# 5_Ble.net
KiCad netlist of a schematic drawn in Altium Designer
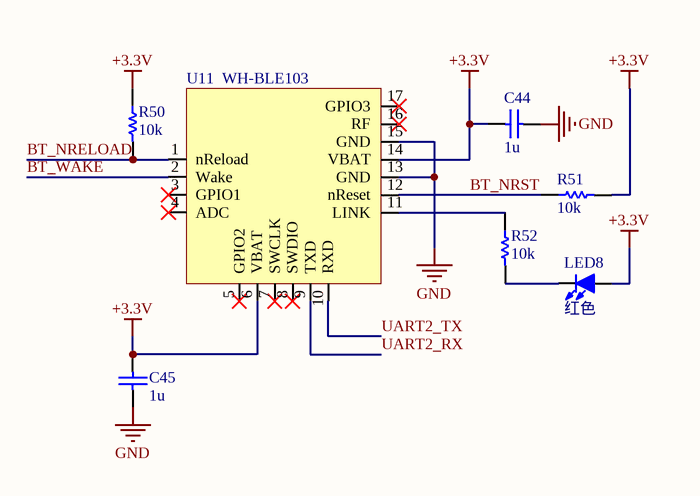
[diagram p0: 5_Ble.SchDoc]

(export (version "E")
  (design (tool "Eeschema 10.0.6"))
  (components
    (comp (ref "C44")
      (value "1u")
      (footprint "CAP_0603_SMD")
      (description "Capacitor, 0603, SMD")
      (fields (field (name "PUBLISHER") "Altium Limited"))
      (libsource (lib "myRLC") (part "CAP_0603_SMD"))
    )
    (comp (ref "C45")
      (value "1u")
      (footprint "CAP_0603_SMD")
      (description "Capacitor, 0603, SMD")
      (fields (field (name "PUBLISHER") "Altium Limited"))
      (libsource (lib "myRLC") (part "CAP_0603_SMD"))
    )
    (comp (ref "LED8")
      (value "红色")
      (footprint "LED0603_Y")
      (description "贴片LED")
      (libsource (lib "0.3 - LED发光二极管") (part "LED-SMD"))
    )
    (comp (ref "R50")
      (value "10k")
      (footprint "RES_0603_SMD")
      (description "Resistor, 0603, SMD")
      (fields (field (name "PUBLISHER") "Altium Limited"))
      (libsource (lib "myRLC") (part "RES_0603_SMD"))
    )
    (comp (ref "R51")
      (value "10k")
      (footprint "RES_0603_SMD")
      (description "Resistor, 0603, SMD")
      (fields (field (name "PUBLISHER") "Altium Limited"))
      (libsource (lib "myRLC") (part "RES_0603_SMD"))
    )
    (comp (ref "R52")
      (value "10k")
      (footprint "RES_0603_SMD")
      (description "Resistor, 0603, SMD")
      (fields (field (name "PUBLISHER") "Altium Limited"))
      (libsource (lib "myRLC") (part "RES_0603_SMD"))
    )
    (comp (ref "U11")
      (value "WH-BLE103")
      (footprint "WH-BLE103:PCBComponent_1")
      (libsource (lib "WH-BLE103") (part "WH-BLE103"))
    )
  )
  (nets
    (net (code "1") (name "+3.3V") (class "Default")
      (node (ref "C44") (pin "2") (pinfunction "2_2") (pintype "passive"))
      (node (ref "C45") (pin "1") (pinfunction "1_1") (pintype "passive"))
      (node (ref "LED8") (pin "1") (pinfunction "A_1") (pintype "passive"))
      (node (ref "R50") (pin "1") (pinfunction "1_1") (pintype "passive"))
      (node (ref "R51") (pin "2") (pinfunction "2_2") (pintype "passive"))
      (node (ref "U11") (pin "14") (pinfunction "VBAT_14") (pintype "passive"))
      (node (ref "U11") (pin "6") (pinfunction "VBAT_6") (pintype "passive"))
    )
    (net (code "2") (name "/BT_NRELOAD") (class "Default")
      (node (ref "R50") (pin "2") (pinfunction "2_2") (pintype "passive"))
      (node (ref "U11") (pin "1") (pinfunction "nReload_1") (pintype "passive"))
    )
    (net (code "3") (name "/BT_NRST") (class "Default")
      (node (ref "R51") (pin "1") (pinfunction "1_1") (pintype "passive"))
      (node (ref "U11") (pin "12") (pinfunction "nReset_12") (pintype "passive"))
    )
    (net (code "4") (name "/BT_WAKE") (class "Default")
      (node (ref "U11") (pin "2") (pinfunction "Wake_2") (pintype "passive"))
    )
    (net (code "5") (name "/UART2_RX") (class "Default")
      (node (ref "U11") (pin "9") (pinfunction "TXD_9") (pintype "passive"))
    )
    (net (code "6") (name "/UART2_TX") (class "Default")
      (node (ref "U11") (pin "10") (pinfunction "RXD_10") (pintype "passive"))
    )
    (net (code "7") (name "GND") (class "Default")
      (node (ref "C44") (pin "1") (pinfunction "1_1") (pintype "passive"))
      (node (ref "C45") (pin "2") (pinfunction "2_2") (pintype "passive"))
      (node (ref "U11") (pin "13") (pinfunction "GND_13") (pintype "passive"))
      (node (ref "U11") (pin "15") (pinfunction "GND_15") (pintype "passive"))
    )
    (net (code "8") (name "Net-(LED8-K)") (class "Default")
      (node (ref "LED8") (pin "2") (pinfunction "K_2") (pintype "passive"))
      (node (ref "R52") (pin "2") (pinfunction "2_2") (pintype "passive"))
    )
    (net (code "9") (name "Net-(U11-LINK)") (class "Default")
      (node (ref "R52") (pin "1") (pinfunction "1_1") (pintype "passive"))
      (node (ref "U11") (pin "11") (pinfunction "LINK_11") (pintype "passive"))
    )
    (net (code "10") (name "unconnected-(U11-ADC-Pad4)") (class "Default")
      (node (ref "U11") (pin "4") (pinfunction "ADC_4") (pintype "passive+no_connect"))
    )
    (net (code "11") (name "unconnected-(U11-GPIO1-Pad3)") (class "Default")
      (node (ref "U11") (pin "3") (pinfunction "GPIO1_3") (pintype "passive+no_connect"))
    )
    (net (code "12") (name "unconnected-(U11-GPIO2-Pad5)") (class "Default")
      (node (ref "U11") (pin "5") (pinfunction "GPIO2_5") (pintype "passive+no_connect"))
    )
    (net (code "13") (name "unconnected-(U11-GPIO3-Pad17)") (class "Default")
      (node (ref "U11") (pin "17") (pinfunction "GPIO3_17") (pintype "passive+no_connect"))
    )
    (net (code "14") (name "unconnected-(U11-RF-Pad16)") (class "Default")
      (node (ref "U11") (pin "16") (pinfunction "RF_16") (pintype "passive+no_connect"))
    )
    (net (code "15") (name "unconnected-(U11-SWCLK-Pad7)") (class "Default")
      (node (ref "U11") (pin "7") (pinfunction "SWCLK_7") (pintype "passive+no_connect"))
    )
    (net (code "16") (name "unconnected-(U11-SWDIO-Pad8)") (class "Default")
      (node (ref "U11") (pin "8") (pinfunction "SWDIO_8") (pintype "passive+no_connect"))
    )
  )
)
